# FMC_connector.net
KiCad netlist of a schematic drawn in Altium Designer
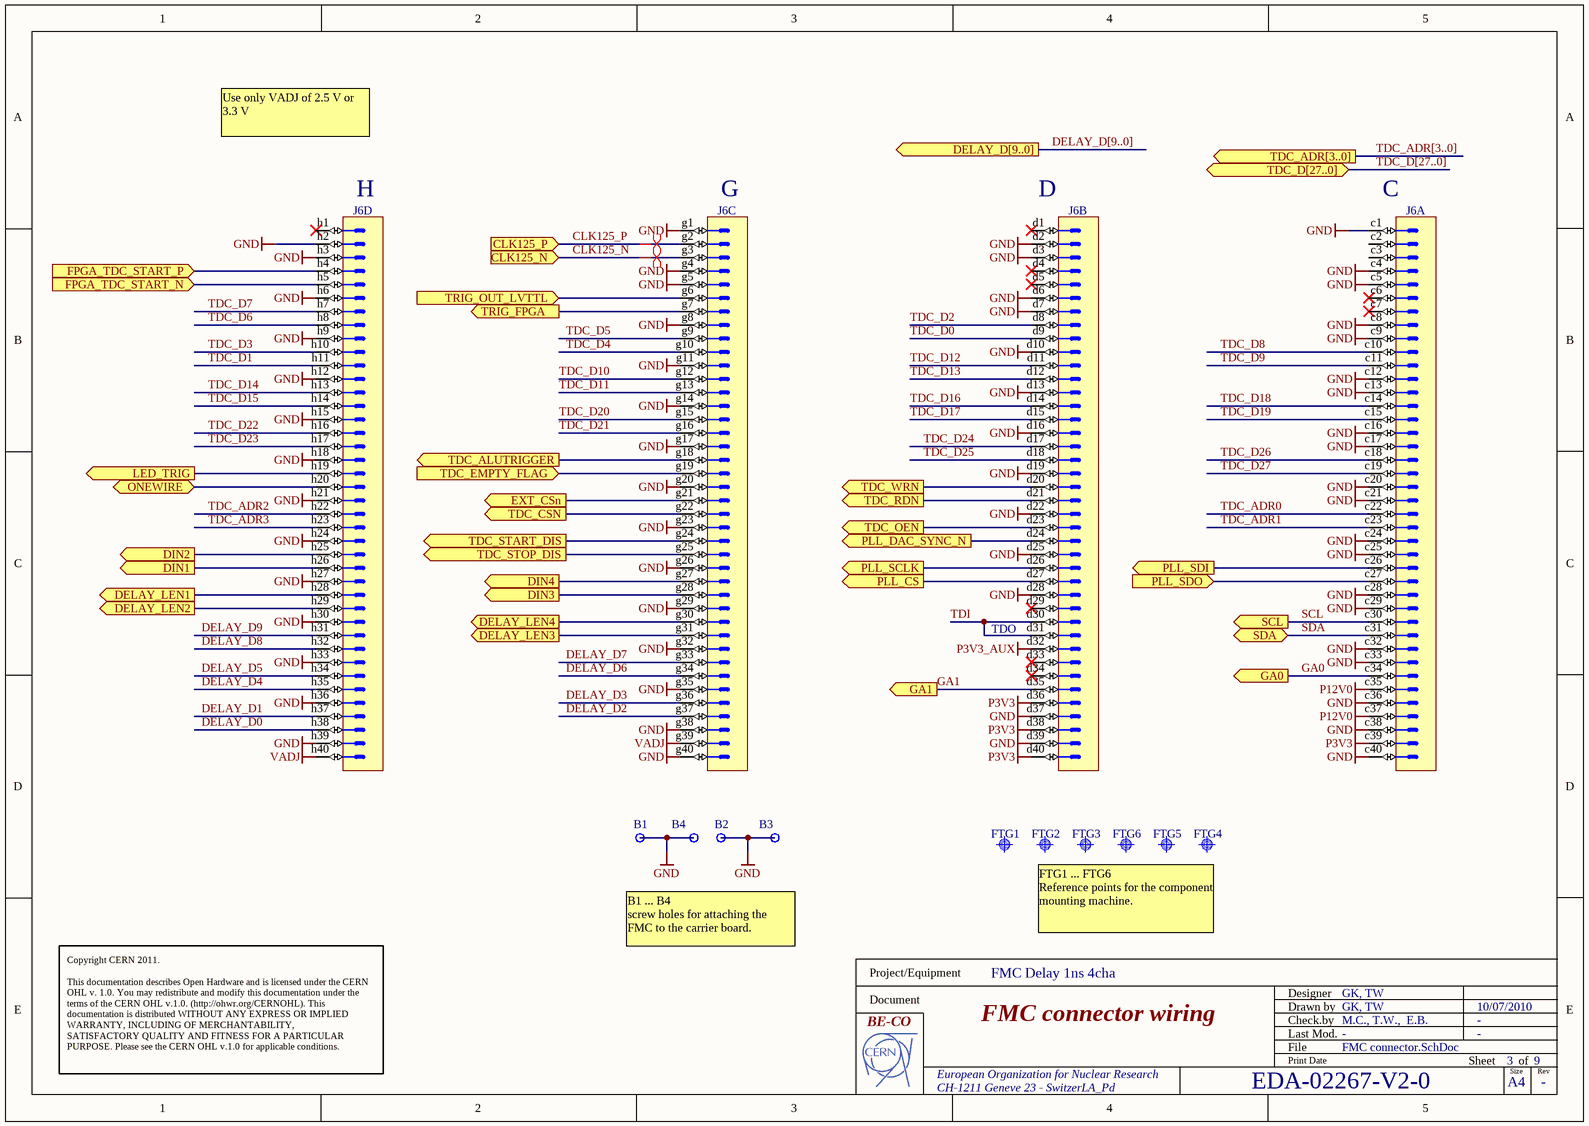
[diagram p0: FMC connector.SchDoc]

(export (version "E")
  (design (tool "Eeschema 10.0.6"))
  (components
    (comp (ref "B1")
      (value "Plated Hole")
      (footprint "MTG300_600")
      (description "Single Terminal Socket")
      (fields (field (name "PART NUMBER") "PLATED_HOLE3.0_PAD6.0") (field (name "AUTHOR") "CERN DEM JLC"))
      (libsource (lib "Eletro-mechanical") (part "Single Terminal Socket"))
    )
    (comp (ref "B2")
      (value "Plated Hole")
      (footprint "MTG300_600")
      (description "Single Terminal Socket")
      (fields (field (name "PART NUMBER") "PLATED_HOLE3.0_PAD6.0") (field (name "AUTHOR") "CERN DEM JLC"))
      (libsource (lib "Eletro-mechanical") (part "Single Terminal Socket"))
    )
    (comp (ref "B3")
      (value "Plated Hole")
      (footprint "MTG300_600")
      (description "Single Terminal Socket")
      (fields (field (name "PART NUMBER") "PLATED_HOLE3.0_PAD6.0") (field (name "AUTHOR") "CERN DEM JLC"))
      (libsource (lib "Eletro-mechanical") (part "Single Terminal Socket"))
    )
    (comp (ref "B4")
      (value "Plated Hole")
      (footprint "MTG300_600")
      (description "Single Terminal Socket")
      (fields (field (name "PART NUMBER") "PLATED_HOLE3.0_PAD6.0") (field (name "AUTHOR") "CERN DEM JLC"))
      (libsource (lib "Eletro-mechanical") (part "Single Terminal Socket"))
    )
    (comp (ref "FTG1")
      (value "Use only in PCB")
      (footprint "FIDUCIAL_TOP_S100-200")
      (description "Fiducial Target")
      (fields (field (name "PART NUMBER") "FIDUCIAL_TARGET_S100-200") (field (name "AUTHOR") "CERN DEM JLC"))
      (libsource (lib "Eletro-mechanical") (part "Fiducial Target"))
    )
    (comp (ref "FTG2")
      (value "Use only in PCB")
      (footprint "FIDUCIAL_TOP_S100-200")
      (description "Fiducial Target")
      (fields (field (name "PART NUMBER") "FIDUCIAL_TARGET_S100-200") (field (name "AUTHOR") "CERN DEM JLC"))
      (libsource (lib "Eletro-mechanical") (part "Fiducial Target"))
    )
    (comp (ref "FTG3")
      (value "Use only in PCB")
      (footprint "FIDUCIAL_TOP_S100-200")
      (description "Fiducial Target")
      (fields (field (name "PART NUMBER") "FIDUCIAL_TARGET_S100-200") (field (name "AUTHOR") "CERN DEM JLC"))
      (libsource (lib "Eletro-mechanical") (part "Fiducial Target"))
    )
    (comp (ref "FTG4")
      (value "Use only in PCB")
      (footprint "FIDUCIAL_TOP_S100-200")
      (description "Fiducial Target")
      (fields (field (name "PART NUMBER") "FIDUCIAL_TARGET_S100-200") (field (name "AUTHOR") "CERN DEM JLC"))
      (libsource (lib "Eletro-mechanical") (part "Fiducial Target"))
    )
    (comp (ref "FTG5")
      (value "Use only in PCB")
      (footprint "FIDUCIAL_TOP_S100-200")
      (description "Fiducial Target")
      (fields (field (name "PART NUMBER") "FIDUCIAL_TARGET_S100-200") (field (name "AUTHOR") "CERN DEM JLC"))
      (libsource (lib "Eletro-mechanical") (part "Fiducial Target"))
    )
    (comp (ref "FTG6")
      (value "Use only in PCB")
      (footprint "FIDUCIAL_TOP_S100-200")
      (description "Fiducial Target")
      (fields (field (name "PART NUMBER") "FIDUCIAL_TARGET_S100-200") (field (name "AUTHOR") "CERN DEM JLC"))
      (libsource (lib "Eletro-mechanical") (part "Fiducial Target"))
    )
    (comp (ref "J6")
      (value "VITA 57")
      (footprint "SAMTEC_ASP-127797-01")
      (description "Connector VITA 57, 160 Male contacts in 4 row cdgh")
      (fields
        (field (name "PART NUMBER") "SAMTEC_ASP-127797-01")
        (field (name "MANUFACTURER") "SAMTEC")
        (field (name "AUTHOR") "CERN DEM JLC")
      )
      (libsource (lib "Connectors") (part "Connector VITA 57 160 Male (cdgh)"))
    )
  )
  (nets
    (net (code "1") (name "/CLK125_N") (class "Default")
      (node (ref "J6") (pin "g3") (pinfunction "g3_g3") (pintype "bidirectional"))
    )
    (net (code "2") (name "/CLK125_P") (class "Default")
      (node (ref "J6") (pin "g2") (pinfunction "g2_g2") (pintype "bidirectional"))
    )
    (net (code "3") (name "/DELAY_D0") (class "Default")
      (node (ref "J6") (pin "h38") (pinfunction "h38_h38") (pintype "bidirectional"))
    )
    (net (code "4") (name "/DELAY_D1") (class "Default")
      (node (ref "J6") (pin "h37") (pinfunction "h37_h37") (pintype "bidirectional"))
    )
    (net (code "5") (name "/DELAY_D2") (class "Default")
      (node (ref "J6") (pin "g37") (pinfunction "g37_g37") (pintype "bidirectional"))
    )
    (net (code "6") (name "/DELAY_D3") (class "Default")
      (node (ref "J6") (pin "g36") (pinfunction "g36_g36") (pintype "bidirectional"))
    )
    (net (code "7") (name "/DELAY_D4") (class "Default")
      (node (ref "J6") (pin "h35") (pinfunction "h35_h35") (pintype "bidirectional"))
    )
    (net (code "8") (name "/DELAY_D5") (class "Default")
      (node (ref "J6") (pin "h34") (pinfunction "h34_h34") (pintype "bidirectional"))
    )
    (net (code "9") (name "/DELAY_D6") (class "Default")
      (node (ref "J6") (pin "g34") (pinfunction "g34_g34") (pintype "bidirectional"))
    )
    (net (code "10") (name "/DELAY_D7") (class "Default")
      (node (ref "J6") (pin "g33") (pinfunction "g33_g33") (pintype "bidirectional"))
    )
    (net (code "11") (name "/DELAY_D8") (class "Default")
      (node (ref "J6") (pin "h32") (pinfunction "h32_h32") (pintype "bidirectional"))
    )
    (net (code "12") (name "/DELAY_D9") (class "Default")
      (node (ref "J6") (pin "h31") (pinfunction "h31_h31") (pintype "bidirectional"))
    )
    (net (code "14") (name "/DELAY_LEN1") (class "Default")
      (node (ref "J6") (pin "h28") (pinfunction "h28_h28") (pintype "bidirectional"))
    )
    (net (code "15") (name "/DELAY_LEN2") (class "Default")
      (node (ref "J6") (pin "h29") (pinfunction "h29_h29") (pintype "bidirectional"))
    )
    (net (code "16") (name "/DELAY_LEN3") (class "Default")
      (node (ref "J6") (pin "g31") (pinfunction "g31_g31") (pintype "bidirectional"))
    )
    (net (code "17") (name "/DELAY_LEN4") (class "Default")
      (node (ref "J6") (pin "g30") (pinfunction "g30_g30") (pintype "bidirectional"))
    )
    (net (code "18") (name "/DIN1") (class "Default")
      (node (ref "J6") (pin "h26") (pinfunction "h26_h26") (pintype "bidirectional"))
    )
    (net (code "19") (name "/DIN2") (class "Default")
      (node (ref "J6") (pin "h25") (pinfunction "h25_h25") (pintype "bidirectional"))
    )
    (net (code "20") (name "/DIN3") (class "Default")
      (node (ref "J6") (pin "g28") (pinfunction "g28_g28") (pintype "bidirectional"))
    )
    (net (code "21") (name "/DIN4") (class "Default")
      (node (ref "J6") (pin "g27") (pinfunction "g27_g27") (pintype "bidirectional"))
    )
    (net (code "22") (name "/EXT_CSn") (class "Default")
      (node (ref "J6") (pin "g21") (pinfunction "g21_g21") (pintype "bidirectional"))
    )
    (net (code "23") (name "/FPGA_TDC_START_N") (class "Default")
      (node (ref "J6") (pin "h5") (pinfunction "h5_h5") (pintype "bidirectional"))
    )
    (net (code "24") (name "/FPGA_TDC_START_P") (class "Default")
      (node (ref "J6") (pin "h4") (pinfunction "h4_h4") (pintype "bidirectional"))
    )
    (net (code "25") (name "/GA0") (class "Default")
      (node (ref "J6") (pin "c34") (pinfunction "c34_c34") (pintype "bidirectional"))
    )
    (net (code "26") (name "/GA1") (class "Default")
      (node (ref "J6") (pin "d35") (pinfunction "d35_d35") (pintype "bidirectional"))
    )
    (net (code "27") (name "/LED_TRIG") (class "Default")
      (node (ref "J6") (pin "h19") (pinfunction "h19_h19") (pintype "bidirectional"))
    )
    (net (code "28") (name "/ONEWIRE") (class "Default")
      (node (ref "J6") (pin "h20") (pinfunction "h20_h20") (pintype "bidirectional"))
    )
    (net (code "29") (name "/PLL_CS") (class "Default")
      (node (ref "J6") (pin "d27") (pinfunction "d27_d27") (pintype "bidirectional"))
    )
    (net (code "30") (name "/PLL_DAC_SYNC_N") (class "Default")
      (node (ref "J6") (pin "d24") (pinfunction "d24_d24") (pintype "bidirectional"))
    )
    (net (code "31") (name "/PLL_SCLK") (class "Default")
      (node (ref "J6") (pin "d26") (pinfunction "d26_d26") (pintype "bidirectional"))
    )
    (net (code "32") (name "/PLL_SDI") (class "Default")
      (node (ref "J6") (pin "c26") (pinfunction "c26_c26") (pintype "bidirectional"))
    )
    (net (code "33") (name "/PLL_SDO") (class "Default")
      (node (ref "J6") (pin "c27") (pinfunction "c27_c27") (pintype "bidirectional"))
    )
    (net (code "34") (name "/SCL") (class "Default")
      (node (ref "J6") (pin "c30") (pinfunction "c30_c30") (pintype "bidirectional"))
    )
    (net (code "35") (name "/SDA") (class "Default")
      (node (ref "J6") (pin "c31") (pinfunction "c31_c31") (pintype "bidirectional"))
    )
    (net (code "36") (name "/TDC_ADR0") (class "Default")
      (node (ref "J6") (pin "c22") (pinfunction "c22_c22") (pintype "bidirectional"))
    )
    (net (code "37") (name "/TDC_ADR1") (class "Default")
      (node (ref "J6") (pin "c23") (pinfunction "c23_c23") (pintype "bidirectional"))
    )
    (net (code "38") (name "/TDC_ADR2") (class "Default")
      (node (ref "J6") (pin "h22") (pinfunction "h22_h22") (pintype "bidirectional"))
    )
    (net (code "39") (name "/TDC_ADR3") (class "Default")
      (node (ref "J6") (pin "h23") (pinfunction "h23_h23") (pintype "bidirectional"))
    )
    (net (code "41") (name "/TDC_ALUTRIGGER") (class "Default")
      (node (ref "J6") (pin "g18") (pinfunction "g18_g18") (pintype "bidirectional"))
    )
    (net (code "42") (name "/TDC_CSN") (class "Default")
      (node (ref "J6") (pin "g22") (pinfunction "g22_g22") (pintype "bidirectional"))
    )
    (net (code "43") (name "/TDC_D0") (class "Default")
      (node (ref "J6") (pin "d9") (pinfunction "d9_d9") (pintype "bidirectional"))
    )
    (net (code "44") (name "/TDC_D1") (class "Default")
      (node (ref "J6") (pin "h11") (pinfunction "h11_h11") (pintype "bidirectional"))
    )
    (net (code "45") (name "/TDC_D2") (class "Default")
      (node (ref "J6") (pin "d8") (pinfunction "d8_d8") (pintype "bidirectional"))
    )
    (net (code "46") (name "/TDC_D3") (class "Default")
      (node (ref "J6") (pin "h10") (pinfunction "h10_h10") (pintype "bidirectional"))
    )
    (net (code "47") (name "/TDC_D4") (class "Default")
      (node (ref "J6") (pin "g10") (pinfunction "g10_g10") (pintype "bidirectional"))
    )
    (net (code "48") (name "/TDC_D5") (class "Default")
      (node (ref "J6") (pin "g9") (pinfunction "g9_g9") (pintype "bidirectional"))
    )
    (net (code "49") (name "/TDC_D6") (class "Default")
      (node (ref "J6") (pin "h8") (pinfunction "h8_h8") (pintype "bidirectional"))
    )
    (net (code "50") (name "/TDC_D7") (class "Default")
      (node (ref "J6") (pin "h7") (pinfunction "h7_h7") (pintype "bidirectional"))
    )
    (net (code "51") (name "/TDC_D8") (class "Default")
      (node (ref "J6") (pin "c10") (pinfunction "c10_c10") (pintype "bidirectional"))
    )
    (net (code "52") (name "/TDC_D9") (class "Default")
      (node (ref "J6") (pin "c11") (pinfunction "c11_c11") (pintype "bidirectional"))
    )
    (net (code "53") (name "/TDC_D10") (class "Default")
      (node (ref "J6") (pin "g12") (pinfunction "g12_g12") (pintype "bidirectional"))
    )
    (net (code "54") (name "/TDC_D11") (class "Default")
      (node (ref "J6") (pin "g13") (pinfunction "g13_g13") (pintype "bidirectional"))
    )
    (net (code "55") (name "/TDC_D12") (class "Default")
      (node (ref "J6") (pin "d11") (pinfunction "d11_d11") (pintype "bidirectional"))
    )
    (net (code "56") (name "/TDC_D13") (class "Default")
      (node (ref "J6") (pin "d12") (pinfunction "d12_d12") (pintype "bidirectional"))
    )
    (net (code "57") (name "/TDC_D14") (class "Default")
      (node (ref "J6") (pin "h13") (pinfunction "h13_h13") (pintype "bidirectional"))
    )
    (net (code "58") (name "/TDC_D15") (class "Default")
      (node (ref "J6") (pin "h14") (pinfunction "h14_h14") (pintype "bidirectional"))
    )
    (net (code "59") (name "/TDC_D16") (class "Default")
      (node (ref "J6") (pin "d14") (pinfunction "d14_d14") (pintype "bidirectional"))
    )
    (net (code "60") (name "/TDC_D17") (class "Default")
      (node (ref "J6") (pin "d15") (pinfunction "d15_d15") (pintype "bidirectional"))
    )
    (net (code "61") (name "/TDC_D18") (class "Default")
      (node (ref "J6") (pin "c14") (pinfunction "c14_c14") (pintype "bidirectional"))
    )
    (net (code "62") (name "/TDC_D19") (class "Default")
      (node (ref "J6") (pin "c15") (pinfunction "c15_c15") (pintype "bidirectional"))
    )
    (net (code "63") (name "/TDC_D20") (class "Default")
      (node (ref "J6") (pin "g15") (pinfunction "g15_g15") (pintype "bidirectional"))
    )
    (net (code "64") (name "/TDC_D21") (class "Default")
      (node (ref "J6") (pin "g16") (pinfunction "g16_g16") (pintype "bidirectional"))
    )
    (net (code "65") (name "/TDC_D22") (class "Default")
      (node (ref "J6") (pin "h16") (pinfunction "h16_h16") (pintype "bidirectional"))
    )
    (net (code "66") (name "/TDC_D23") (class "Default")
      (node (ref "J6") (pin "h17") (pinfunction "h17_h17") (pintype "bidirectional"))
    )
    (net (code "67") (name "/TDC_D24") (class "Default")
      (node (ref "J6") (pin "d17") (pinfunction "d17_d17") (pintype "bidirectional"))
    )
    (net (code "68") (name "/TDC_D25") (class "Default")
      (node (ref "J6") (pin "d18") (pinfunction "d18_d18") (pintype "bidirectional"))
    )
    (net (code "69") (name "/TDC_D26") (class "Default")
      (node (ref "J6") (pin "c18") (pinfunction "c18_c18") (pintype "bidirectional"))
    )
    (net (code "70") (name "/TDC_D27") (class "Default")
      (node (ref "J6") (pin "c19") (pinfunction "c19_c19") (pintype "bidirectional"))
    )
    (net (code "72") (name "/TDC_EMPTY_FLAG") (class "Default")
      (node (ref "J6") (pin "g19") (pinfunction "g19_g19") (pintype "bidirectional"))
    )
    (net (code "73") (name "/TDC_OEN") (class "Default")
      (node (ref "J6") (pin "d23") (pinfunction "d23_d23") (pintype "bidirectional"))
    )
    (net (code "74") (name "/TDC_RDN") (class "Default")
      (node (ref "J6") (pin "d21") (pinfunction "d21_d21") (pintype "bidirectional"))
    )
    (net (code "75") (name "/TDC_START_DIS") (class "Default")
      (node (ref "J6") (pin "g24") (pinfunction "g24_g24") (pintype "bidirectional"))
    )
    (net (code "76") (name "/TDC_STOP_DIS") (class "Default")
      (node (ref "J6") (pin "g25") (pinfunction "g25_g25") (pintype "bidirectional"))
    )
    (net (code "77") (name "/TDC_WRN") (class "Default")
      (node (ref "J6") (pin "d20") (pinfunction "d20_d20") (pintype "bidirectional"))
    )
    (net (code "78") (name "/TDI") (class "Default")
      (node (ref "J6") (pin "d30") (pinfunction "d30_d30") (pintype "bidirectional"))
      (node (ref "J6") (pin "d31") (pinfunction "d31_d31") (pintype "bidirectional"))
    )
    (net (code "79") (name "/TRIG_FPGA") (class "Default")
      (node (ref "J6") (pin "g7") (pinfunction "g7_g7") (pintype "bidirectional"))
    )
    (net (code "80") (name "/TRIG_OUT_LVTTL") (class "Default")
      (node (ref "J6") (pin "g6") (pinfunction "g6_g6") (pintype "bidirectional"))
    )
    (net (code "81") (name "GND") (class "Default")
      (node (ref "B1") (pin "1") (pinfunction "1_1") (pintype "bidirectional"))
      (node (ref "B2") (pin "1") (pinfunction "1_1") (pintype "bidirectional"))
      (node (ref "B3") (pin "1") (pinfunction "1_1") (pintype "bidirectional"))
      (node (ref "B4") (pin "1") (pinfunction "1_1") (pintype "bidirectional"))
      (node (ref "J6") (pin "c1") (pinfunction "c1_c1") (pintype "bidirectional"))
      (node (ref "J6") (pin "c12") (pinfunction "c12_c12") (pintype "bidirectional"))
      (node (ref "J6") (pin "c13") (pinfunction "c13_c13") (pintype "bidirectional"))
      (node (ref "J6") (pin "c16") (pinfunction "c16_c16") (pintype "bidirectional"))
      (node (ref "J6") (pin "c17") (pinfunction "c17_c17") (pintype "bidirectional"))
      (node (ref "J6") (pin "c20") (pinfunction "c20_c20") (pintype "bidirectional"))
      (node (ref "J6") (pin "c21") (pinfunction "c21_c21") (pintype "bidirectional"))
      (node (ref "J6") (pin "c24") (pinfunction "c24_c24") (pintype "bidirectional"))
      (node (ref "J6") (pin "c25") (pinfunction "c25_c25") (pintype "bidirectional"))
      (node (ref "J6") (pin "c28") (pinfunction "c28_c28") (pintype "bidirectional"))
      (node (ref "J6") (pin "c29") (pinfunction "c29_c29") (pintype "bidirectional"))
      (node (ref "J6") (pin "c32") (pinfunction "c32_c32") (pintype "bidirectional"))
      (node (ref "J6") (pin "c33") (pinfunction "c33_c33") (pintype "bidirectional"))
      (node (ref "J6") (pin "c36") (pinfunction "c36_c36") (pintype "bidirectional"))
      (node (ref "J6") (pin "c38") (pinfunction "c38_c38") (pintype "bidirectional"))
      (node (ref "J6") (pin "c4") (pinfunction "c4_c4") (pintype "bidirectional"))
      (node (ref "J6") (pin "c40") (pinfunction "c40_c40") (pintype "bidirectional"))
      (node (ref "J6") (pin "c5") (pinfunction "c5_c5") (pintype "bidirectional"))
      (node (ref "J6") (pin "c8") (pinfunction "c8_c8") (pintype "bidirectional"))
      (node (ref "J6") (pin "c9") (pinfunction "c9_c9") (pintype "bidirectional"))
      (node (ref "J6") (pin "d10") (pinfunction "d10_d10") (pintype "bidirectional"))
      (node (ref "J6") (pin "d13") (pinfunction "d13_d13") (pintype "bidirectional"))
      (node (ref "J6") (pin "d16") (pinfunction "d16_d16") (pintype "bidirectional"))
      (node (ref "J6") (pin "d19") (pinfunction "d19_d19") (pintype "bidirectional"))
      (node (ref "J6") (pin "d2") (pinfunction "d2_d2") (pintype "bidirectional"))
      (node (ref "J6") (pin "d22") (pinfunction "d22_d22") (pintype "bidirectional"))
      (node (ref "J6") (pin "d25") (pinfunction "d25_d25") (pintype "bidirectional"))
      (node (ref "J6") (pin "d28") (pinfunction "d28_d28") (pintype "bidirectional"))
      (node (ref "J6") (pin "d3") (pinfunction "d3_d3") (pintype "bidirectional"))
      (node (ref "J6") (pin "d37") (pinfunction "d37_d37") (pintype "bidirectional"))
      (node (ref "J6") (pin "d39") (pinfunction "d39_d39") (pintype "bidirectional"))
      (node (ref "J6") (pin "d6") (pinfunction "d6_d6") (pintype "bidirectional"))
      (node (ref "J6") (pin "d7") (pinfunction "d7_d7") (pintype "bidirectional"))
      (node (ref "J6") (pin "g1") (pinfunction "g1_g1") (pintype "bidirectional"))
      (node (ref "J6") (pin "g11") (pinfunction "g11_g11") (pintype "bidirectional"))
      (node (ref "J6") (pin "g14") (pinfunction "g14_g14") (pintype "bidirectional"))
      (node (ref "J6") (pin "g17") (pinfunction "g17_g17") (pintype "bidirectional"))
      (node (ref "J6") (pin "g20") (pinfunction "g20_g20") (pintype "bidirectional"))
      (node (ref "J6") (pin "g23") (pinfunction "g23_g23") (pintype "bidirectional"))
      (node (ref "J6") (pin "g26") (pinfunction "g26_g26") (pintype "bidirectional"))
      (node (ref "J6") (pin "g29") (pinfunction "g29_g29") (pintype "bidirectional"))
      (node (ref "J6") (pin "g32") (pinfunction "g32_g32") (pintype "bidirectional"))
      (node (ref "J6") (pin "g35") (pinfunction "g35_g35") (pintype "bidirectional"))
      (node (ref "J6") (pin "g38") (pinfunction "g38_g38") (pintype "bidirectional"))
      (node (ref "J6") (pin "g4") (pinfunction "g4_g4") (pintype "bidirectional"))
      (node (ref "J6") (pin "g40") (pinfunction "g40_g40") (pintype "bidirectional"))
      (node (ref "J6") (pin "g5") (pinfunction "g5_g5") (pintype "bidirectional"))
      (node (ref "J6") (pin "g8") (pinfunction "g8_g8") (pintype "bidirectional"))
      (node (ref "J6") (pin "h12") (pinfunction "h12_h12") (pintype "bidirectional"))
      (node (ref "J6") (pin "h15") (pinfunction "h15_h15") (pintype "bidirectional"))
      (node (ref "J6") (pin "h18") (pinfunction "h18_h18") (pintype "bidirectional"))
      (node (ref "J6") (pin "h2") (pinfunction "h2_h2") (pintype "bidirectional"))
      (node (ref "J6") (pin "h21") (pinfunction "h21_h21") (pintype "bidirectional"))
      (node (ref "J6") (pin "h24") (pinfunction "h24_h24") (pintype "bidirectional"))
      (node (ref "J6") (pin "h27") (pinfunction "h27_h27") (pintype "bidirectional"))
      (node (ref "J6") (pin "h3") (pinfunction "h3_h3") (pintype "bidirectional"))
      (node (ref "J6") (pin "h30") (pinfunction "h30_h30") (pintype "bidirectional"))
      (node (ref "J6") (pin "h33") (pinfunction "h33_h33") (pintype "bidirectional"))
      (node (ref "J6") (pin "h36") (pinfunction "h36_h36") (pintype "bidirectional"))
      (node (ref "J6") (pin "h39") (pinfunction "h39_h39") (pintype "bidirectional"))
      (node (ref "J6") (pin "h6") (pinfunction "h6_h6") (pintype "bidirectional"))
      (node (ref "J6") (pin "h9") (pinfunction "h9_h9") (pintype "bidirectional"))
    )
    (net (code "82") (name "P3V3") (class "Default")
      (node (ref "J6") (pin "c39") (pinfunction "c39_c39") (pintype "bidirectional"))
      (node (ref "J6") (pin "d36") (pinfunction "d36_d36") (pintype "bidirectional"))
      (node (ref "J6") (pin "d38") (pinfunction "d38_d38") (pintype "bidirectional"))
      (node (ref "J6") (pin "d40") (pinfunction "d40_d40") (pintype "bidirectional"))
    )
    (net (code "83") (name "P3V3_AUX") (class "Default")
      (node (ref "J6") (pin "d32") (pinfunction "d32_d32") (pintype "bidirectional"))
    )
    (net (code "84") (name "P12V0") (class "Default")
      (node (ref "J6") (pin "c35") (pinfunction "c35_c35") (pintype "bidirectional"))
      (node (ref "J6") (pin "c37") (pinfunction "c37_c37") (pintype "bidirectional"))
    )
    (net (code "85") (name "VADJ") (class "Default")
      (node (ref "J6") (pin "g39") (pinfunction "g39_g39") (pintype "bidirectional"))
      (node (ref "J6") (pin "h40") (pinfunction "h40_h40") (pintype "bidirectional"))
    )
    (net (code "86") (name "unconnected-(J6-Padc2)") (class "Default")
      (node (ref "J6") (pin "c2") (pinfunction "c2_c2") (pintype "bidirectional"))
    )
    (net (code "87") (name "unconnected-(J6-Padc3)") (class "Default")
      (node (ref "J6") (pin "c3") (pinfunction "c3_c3") (pintype "bidirectional"))
    )
    (net (code "88") (name "unconnected-(J6-Padc6)") (class "Default")
      (node (ref "J6") (pin "c6") (pinfunction "c6_c6") (pintype "bidirectional+no_connect"))
    )
    (net (code "89") (name "unconnected-(J6-Padc7)") (class "Default")
      (node (ref "J6") (pin "c7") (pinfunction "c7_c7") (pintype "bidirectional+no_connect"))
    )
    (net (code "90") (name "unconnected-(J6-Padd1)") (class "Default")
      (node (ref "J6") (pin "d1") (pinfunction "d1_d1") (pintype "bidirectional+no_connect"))
    )
    (net (code "91") (name "unconnected-(J6-Padd4)") (class "Default")
      (node (ref "J6") (pin "d4") (pinfunction "d4_d4") (pintype "bidirectional+no_connect"))
    )
    (net (code "92") (name "unconnected-(J6-Padd5)") (class "Default")
      (node (ref "J6") (pin "d5") (pinfunction "d5_d5") (pintype "bidirectional+no_connect"))
    )
    (net (code "93") (name "unconnected-(J6-Padd29)") (class "Default")
      (node (ref "J6") (pin "d29") (pinfunction "d29_d29") (pintype "bidirectional+no_connect"))
    )
    (net (code "94") (name "unconnected-(J6-Padd33)") (class "Default")
      (node (ref "J6") (pin "d33") (pinfunction "d33_d33") (pintype "bidirectional+no_connect"))
    )
    (net (code "95") (name "unconnected-(J6-Padd34)") (class "Default")
      (node (ref "J6") (pin "d34") (pinfunction "d34_d34") (pintype "bidirectional+no_connect"))
    )
    (net (code "96") (name "unconnected-(J6-Padh1)") (class "Default")
      (node (ref "J6") (pin "h1") (pinfunction "h1_h1") (pintype "bidirectional+no_connect"))
    )
  )
)
